# filtre_40kHz.net
KiCad netlist of a schematic drawn in EAGLE
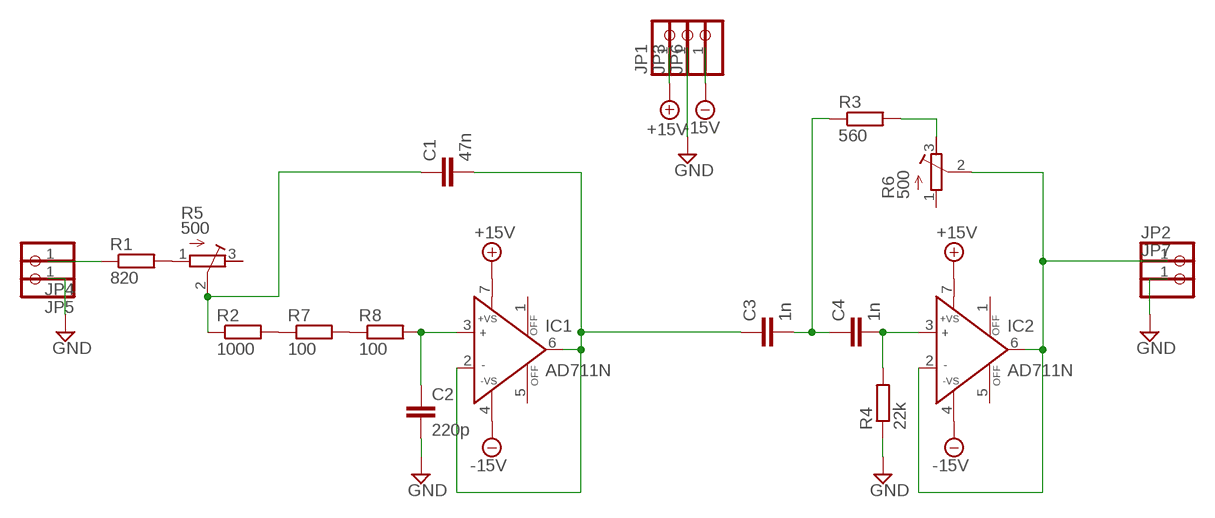
[diagram p0: schematic, sheet 1]

(export (version "E")
  (design (tool "Eeschema 10.0.6"))
  (components
    (comp (ref "C1")
      (value "47n")
      (footprint "eagle-import:C050-024X044")
      (libsource (lib "eagle-import") (part "C-EU050-024X044"))
    )
    (comp (ref "C2")
      (value "220p")
      (footprint "eagle-import:C050-024X044")
      (libsource (lib "eagle-import") (part "C-EU050-024X044"))
    )
    (comp (ref "C3")
      (value "1n")
      (footprint "eagle-import:C075-032X103")
      (libsource (lib "eagle-import") (part "C-EU075-032X103"))
    )
    (comp (ref "C4")
      (value "1n")
      (footprint "eagle-import:C050-024X044")
      (libsource (lib "eagle-import") (part "C-EU050-024X044"))
    )
    (comp (ref "IC1")
      (value "AD711N")
      (footprint "eagle-import:DIL08")
      (fields (field (name "MPN") "AD711BQ"))
      (libsource (lib "eagle-import") (part "AD711N"))
    )
    (comp (ref "IC2")
      (value "AD711N")
      (footprint "eagle-import:DIL08")
      (fields (field (name "MPN") "AD711BQ"))
      (libsource (lib "eagle-import") (part "AD711N"))
    )
    (comp (ref "JP1")
      (value "PINHD-1X1")
      (footprint "eagle-import:1X01")
      (libsource (lib "eagle-import") (part "PINHD-1X1"))
    )
    (comp (ref "JP2")
      (value "PINHD-1X1")
      (footprint "eagle-import:1X01")
      (libsource (lib "eagle-import") (part "PINHD-1X1"))
    )
    (comp (ref "JP3")
      (value "PINHD-1X1")
      (footprint "eagle-import:1X01")
      (libsource (lib "eagle-import") (part "PINHD-1X1"))
    )
    (comp (ref "JP4")
      (value "PINHD-1X1")
      (footprint "eagle-import:1X01")
      (libsource (lib "eagle-import") (part "PINHD-1X1"))
    )
    (comp (ref "JP5")
      (value "PINHD-1X1")
      (footprint "eagle-import:1X01")
      (libsource (lib "eagle-import") (part "PINHD-1X1"))
    )
    (comp (ref "JP6")
      (value "PINHD-1X1")
      (footprint "eagle-import:1X01")
      (libsource (lib "eagle-import") (part "PINHD-1X1"))
    )
    (comp (ref "JP7")
      (value "PINHD-1X1")
      (footprint "eagle-import:1X01")
      (libsource (lib "eagle-import") (part "PINHD-1X1"))
    )
    (comp (ref "R1")
      (value "820")
      (footprint "eagle-import:0204_7")
      (libsource (lib "eagle-import") (part "R-EU_0204/7"))
    )
    (comp (ref "R2")
      (value "1000")
      (footprint "eagle-import:0204_7")
      (libsource (lib "eagle-import") (part "R-EU_0204/7"))
    )
    (comp (ref "R3")
      (value "560")
      (footprint "eagle-import:0204_7")
      (libsource (lib "eagle-import") (part "R-EU_0204/7"))
    )
    (comp (ref "R4")
      (value "22k")
      (footprint "eagle-import:0204_7")
      (libsource (lib "eagle-import") (part "R-EU_0204/7"))
    )
    (comp (ref "R5")
      (value "500")
      (footprint "eagle-import:RTRIM3339P")
      (libsource (lib "eagle-import") (part "R-TRIMM3339P"))
    )
    (comp (ref "R6")
      (value "500")
      (footprint "eagle-import:RTRIM3339P")
      (libsource (lib "eagle-import") (part "R-TRIMM3339P"))
    )
    (comp (ref "R7")
      (value "100")
      (footprint "eagle-import:0207_2V")
      (libsource (lib "eagle-import") (part "R-EU_0207/2V"))
    )
    (comp (ref "R8")
      (value "100")
      (footprint "eagle-import:0207_2V")
      (libsource (lib "eagle-import") (part "R-EU_0207/2V"))
    )
  )
  (nets
    (net (code "1") (name "+15V") (class "Default")
      (node (ref "IC1") (pin "7") (pinfunction "+VS_7") (pintype "input"))
      (node (ref "IC2") (pin "7") (pinfunction "+VS_7") (pintype "input"))
      (node (ref "JP1") (pin "1") (pinfunction "1_1") (pintype "passive"))
    )
    (net (code "2") (name "-15V") (class "Default")
      (node (ref "IC1") (pin "4") (pinfunction "-VS_4") (pintype "input"))
      (node (ref "IC2") (pin "4") (pinfunction "-VS_4") (pintype "input"))
      (node (ref "JP6") (pin "1") (pinfunction "1_1") (pintype "passive"))
    )
    (net (code "3") (name "GND") (class "Default")
      (node (ref "C2") (pin "2") (pinfunction "2_2") (pintype "passive"))
      (node (ref "JP3") (pin "1") (pinfunction "1_1") (pintype "passive"))
      (node (ref "JP5") (pin "1") (pinfunction "1_1") (pintype "passive"))
      (node (ref "JP7") (pin "1") (pinfunction "1_1") (pintype "passive"))
      (node (ref "R4") (pin "1") (pinfunction "1_1") (pintype "passive"))
    )
    (net (code "4") (name "Net-(C3-Pad2)") (class "Default")
      (node (ref "C3") (pin "2") (pinfunction "2_2") (pintype "passive"))
      (node (ref "C4") (pin "1") (pinfunction "1_1") (pintype "passive"))
      (node (ref "R3") (pin "1") (pinfunction "1_1") (pintype "passive"))
    )
    (net (code "5") (name "Net-(IC1-IN+)") (class "Default")
      (node (ref "C2") (pin "1") (pinfunction "1_1") (pintype "passive"))
      (node (ref "IC1") (pin "3") (pinfunction "IN+_3") (pintype "input"))
      (node (ref "R8") (pin "2") (pinfunction "2_2") (pintype "passive"))
    )
    (net (code "6") (name "Net-(IC1-IN-)") (class "Default")
      (node (ref "C1") (pin "2") (pinfunction "2_2") (pintype "passive"))
      (node (ref "C3") (pin "1") (pinfunction "1_1") (pintype "passive"))
      (node (ref "IC1") (pin "2") (pinfunction "IN-_2") (pintype "input"))
      (node (ref "IC1") (pin "6") (pinfunction "OUT_6") (pintype "output"))
    )
    (net (code "7") (name "Net-(IC2-IN+)") (class "Default")
      (node (ref "C4") (pin "2") (pinfunction "2_2") (pintype "passive"))
      (node (ref "IC2") (pin "3") (pinfunction "IN+_3") (pintype "input"))
      (node (ref "R4") (pin "2") (pinfunction "2_2") (pintype "passive"))
    )
    (net (code "8") (name "Net-(IC2-IN-)") (class "Default")
      (node (ref "IC2") (pin "2") (pinfunction "IN-_2") (pintype "input"))
      (node (ref "IC2") (pin "6") (pinfunction "OUT_6") (pintype "output"))
      (node (ref "JP2") (pin "1") (pinfunction "1_1") (pintype "passive"))
      (node (ref "R6") (pin "2") (pinfunction "S_2") (pintype "passive"))
    )
    (net (code "9") (name "Net-(JP4-Pad1)") (class "Default")
      (node (ref "JP4") (pin "1") (pinfunction "1_1") (pintype "passive"))
      (node (ref "R1") (pin "1") (pinfunction "1_1") (pintype "passive"))
    )
    (net (code "10") (name "Net-(R2-Pad2)") (class "Default")
      (node (ref "R2") (pin "2") (pinfunction "2_2") (pintype "passive"))
      (node (ref "R7") (pin "1") (pinfunction "1_1") (pintype "passive"))
    )
    (net (code "11") (name "Net-(R5-E)") (class "Default")
      (node (ref "R1") (pin "2") (pinfunction "2_2") (pintype "passive"))
      (node (ref "R5") (pin "1") (pinfunction "E_1") (pintype "passive"))
    )
    (net (code "12") (name "Net-(R5-S)") (class "Default")
      (node (ref "C1") (pin "1") (pinfunction "1_1") (pintype "passive"))
      (node (ref "R2") (pin "1") (pinfunction "1_1") (pintype "passive"))
      (node (ref "R5") (pin "2") (pinfunction "S_2") (pintype "passive"))
    )
    (net (code "13") (name "Net-(R6-A)") (class "Default")
      (node (ref "R3") (pin "2") (pinfunction "2_2") (pintype "passive"))
      (node (ref "R6") (pin "3") (pinfunction "A_3") (pintype "passive"))
    )
    (net (code "14") (name "Net-(R7-Pad2)") (class "Default")
      (node (ref "R7") (pin "2") (pinfunction "2_2") (pintype "passive"))
      (node (ref "R8") (pin "1") (pinfunction "1_1") (pintype "passive"))
    )
    (net (code "15") (name "unconnected-(IC1-OFF-Pad1)") (class "Default")
      (node (ref "IC1") (pin "1") (pinfunction "OFF_1") (pintype "passive"))
    )
    (net (code "16") (name "unconnected-(IC1-OFF-Pad5)") (class "Default")
      (node (ref "IC1") (pin "5") (pinfunction "OFF_5") (pintype "passive"))
    )
    (net (code "17") (name "unconnected-(IC2-OFF-Pad1)") (class "Default")
      (node (ref "IC2") (pin "1") (pinfunction "OFF_1") (pintype "passive"))
    )
    (net (code "18") (name "unconnected-(IC2-OFF-Pad5)") (class "Default")
      (node (ref "IC2") (pin "5") (pinfunction "OFF_5") (pintype "passive"))
    )
    (net (code "19") (name "unconnected-(R5-A-Pad3)") (class "Default")
      (node (ref "R5") (pin "3") (pinfunction "A_3") (pintype "passive"))
    )
    (net (code "20") (name "unconnected-(R6-E-Pad1)") (class "Default")
      (node (ref "R6") (pin "1") (pinfunction "E_1") (pintype "passive"))
    )
  )
)
